# Dashcam_HAT.net
KiCad netlist of a schematic drawn in EAGLE
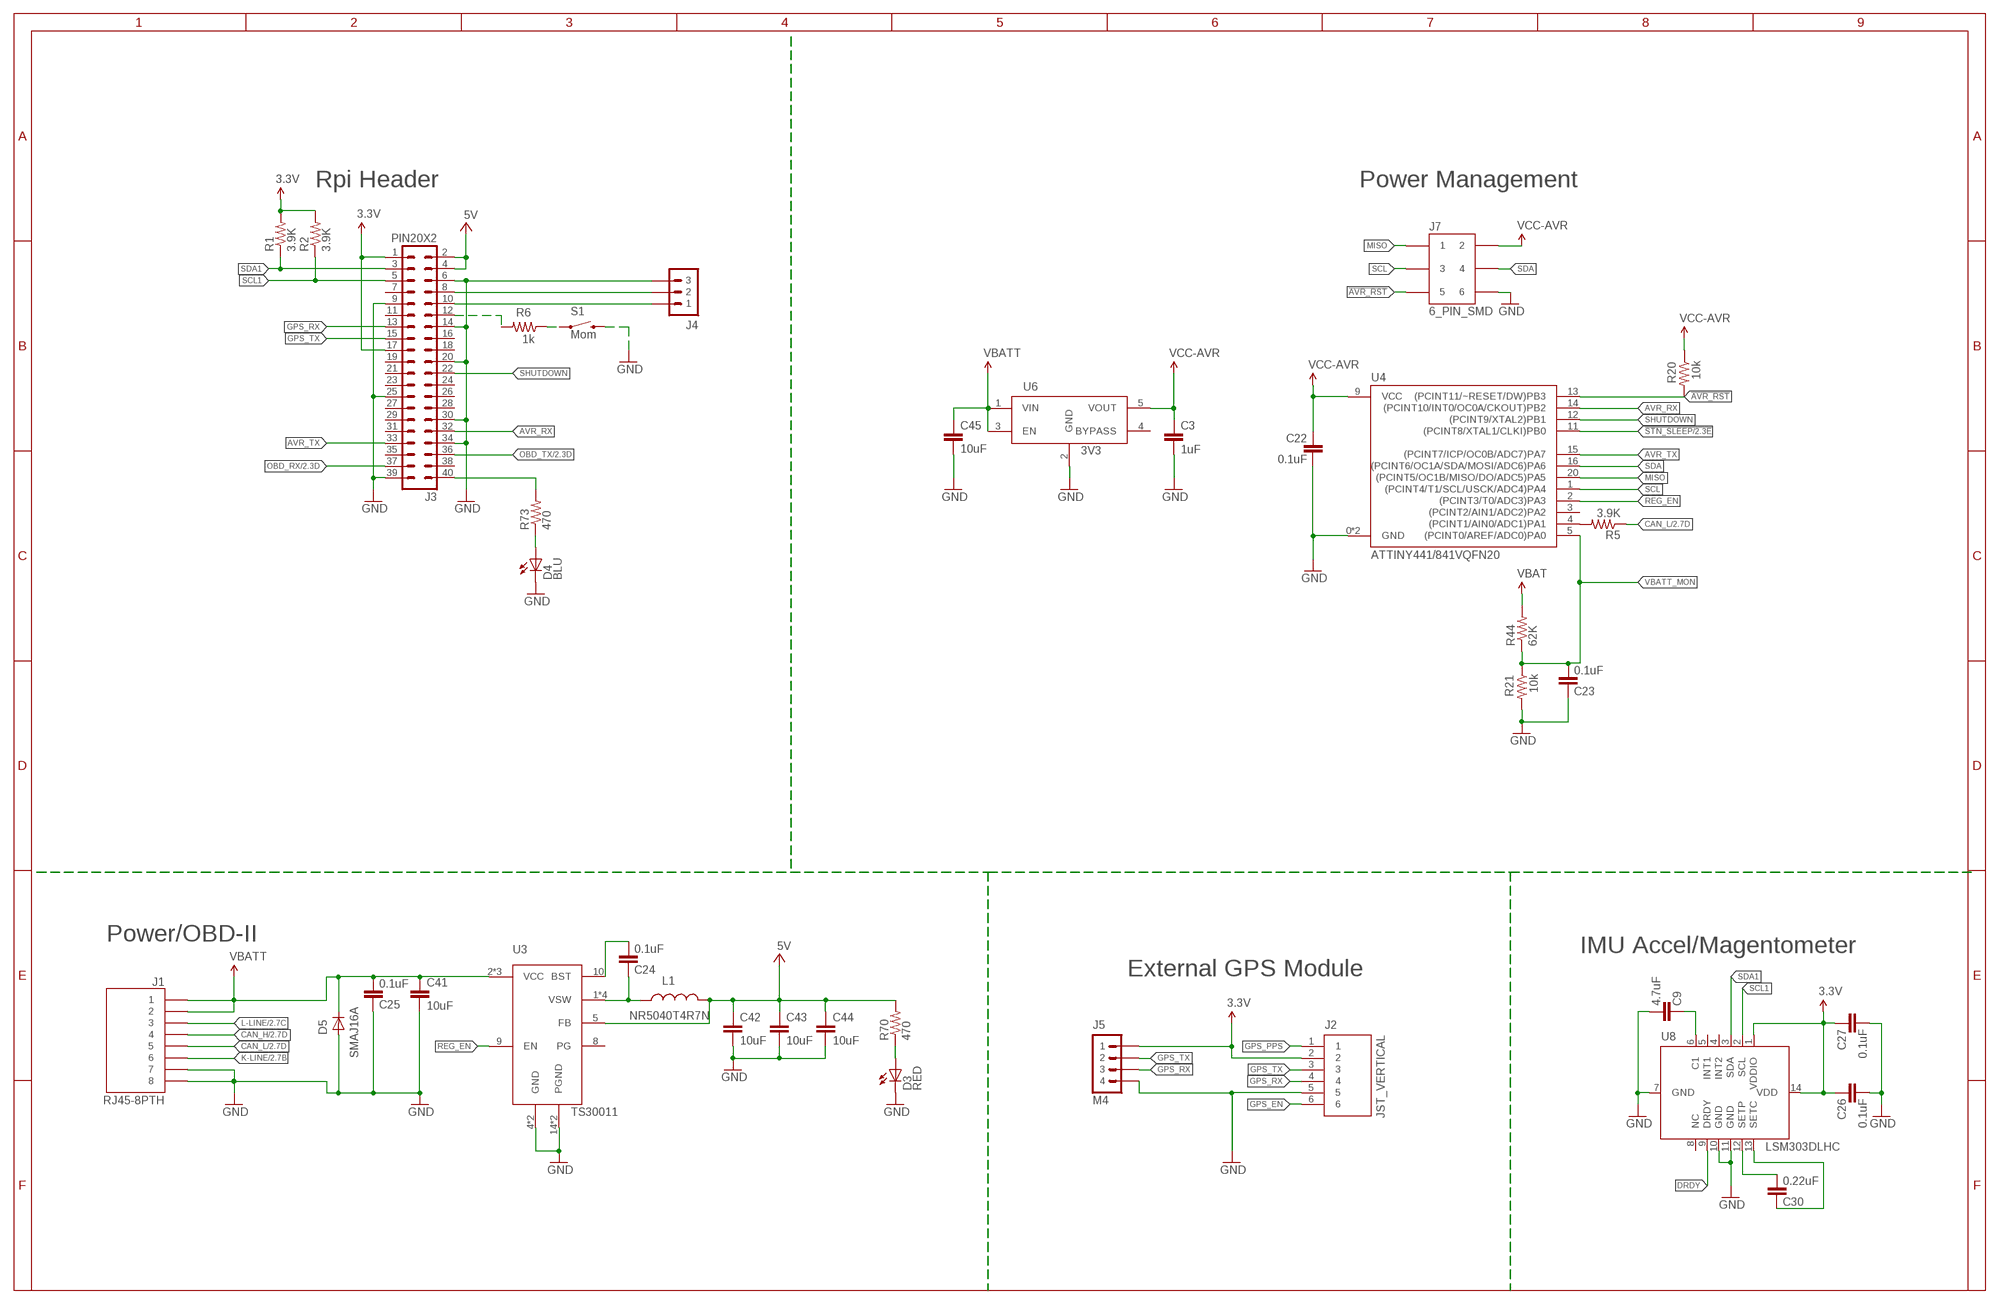
[diagram p0: schematic, sheet 1]
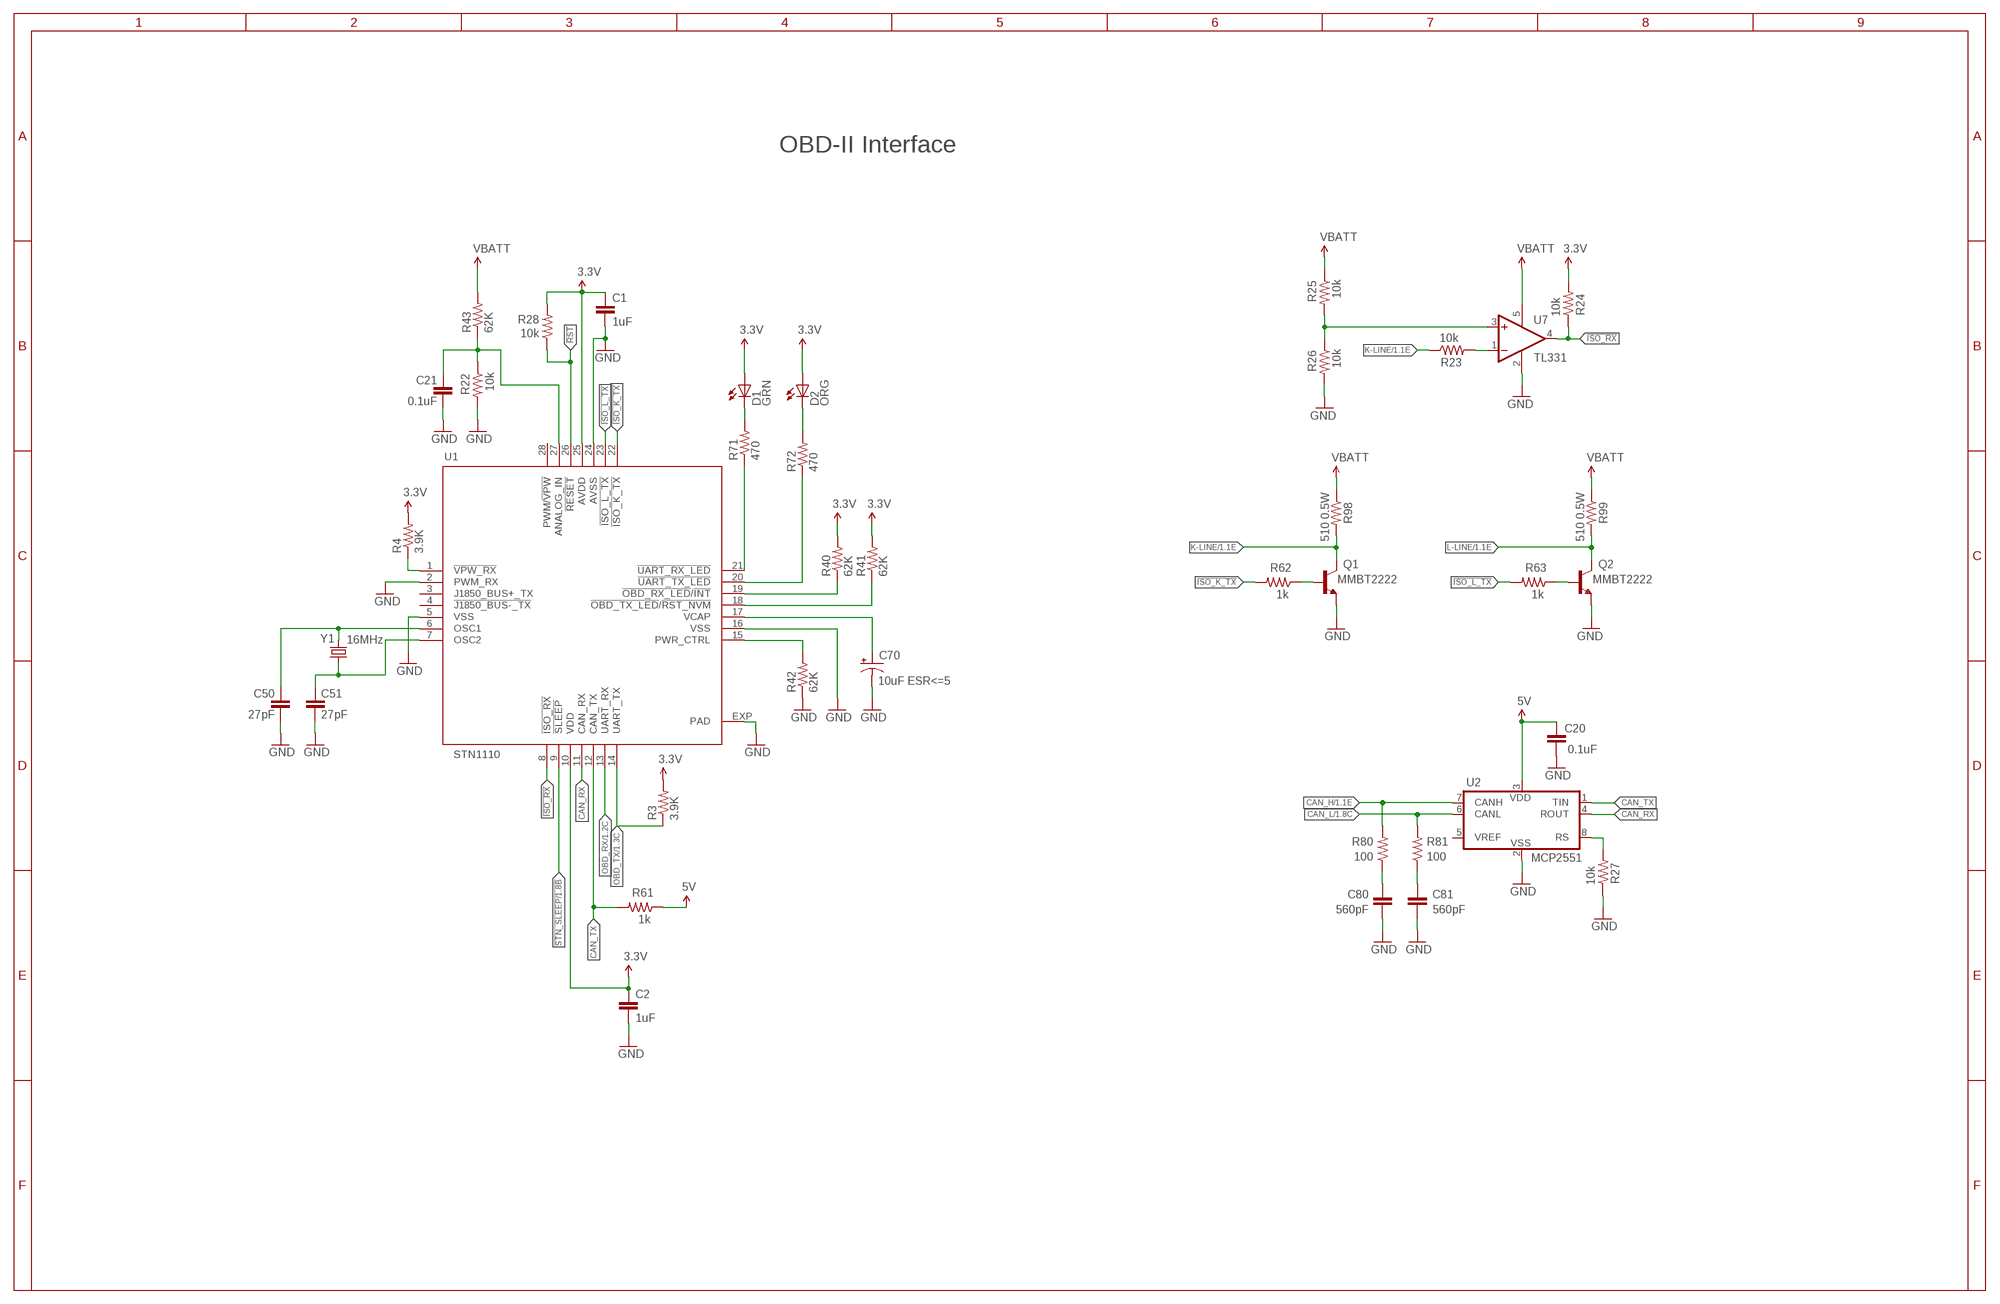
[diagram p1: schematic, sheet 2]

(export (version "E")
  (design (tool "Eeschema 10.0.6"))
  (components
    (comp (ref "C3")
      (value "1uF")
      (footprint "eagle-import:0402-CAP")
      (fields (field (name "MANUFACTURER") "Murata"))
      (libsource (lib "eagle-import") (part "CAP0402-CAP"))
    )
    (comp (ref "C9")
      (value "4.7uF")
      (footprint "eagle-import:0402-CAP")
      (fields (field (name "MANUFACTURER") "Murata"))
      (libsource (lib "eagle-import") (part "CAP0402-CAP"))
    )
    (comp (ref "C22")
      (value "0.1uF")
      (footprint "eagle-import:0402-CAP")
      (fields (field (name "MANUFACTURER") "Samsung"))
      (libsource (lib "eagle-import") (part "CAP0402-CAP"))
    )
    (comp (ref "C23")
      (value "0.1uF")
      (footprint "eagle-import:0402-CAP")
      (fields (field (name "MANUFACTURER") "Samsung"))
      (libsource (lib "eagle-import") (part "CAP0402-CAP"))
    )
    (comp (ref "C24")
      (value "0.1uF")
      (footprint "eagle-import:0402-CAP")
      (fields (field (name "MANUFACTURER") "Samsung"))
      (libsource (lib "eagle-import") (part "CAP0402-CAP"))
    )
    (comp (ref "C25")
      (value "0.1uF")
      (footprint "eagle-import:0402-CAP")
      (fields (field (name "MANUFACTURER") "Samsung"))
      (libsource (lib "eagle-import") (part "CAP0402-CAP"))
    )
    (comp (ref "C26")
      (value "0.1uF")
      (footprint "eagle-import:0402-CAP")
      (fields (field (name "MANUFACTURER") "Samsung"))
      (libsource (lib "eagle-import") (part "CAP0402-CAP"))
    )
    (comp (ref "C27")
      (value "0.1uF")
      (footprint "eagle-import:0402-CAP")
      (fields (field (name "MANUFACTURER") "Samsung"))
      (libsource (lib "eagle-import") (part "CAP0402-CAP"))
    )
    (comp (ref "C30")
      (value "0.22uF")
      (footprint "eagle-import:0402-CAP")
      (fields (field (name "MANUFACTURER") "Murata"))
      (libsource (lib "eagle-import") (part "CAP0402-CAP"))
    )
    (comp (ref "C41")
      (value "10uF")
      (footprint "eagle-import:1206")
      (fields (field (name "MANUFACTURER") "Samsung"))
      (libsource (lib "eagle-import") (part "SparkFun-Capacitors_CAP1206"))
    )
    (comp (ref "C42")
      (value "10uF")
      (footprint "eagle-import:1206")
      (fields (field (name "MANUFACTURER") "Samsung"))
      (libsource (lib "eagle-import") (part "SparkFun-Capacitors_CAP1206"))
    )
    (comp (ref "C43")
      (value "10uF")
      (footprint "eagle-import:1206")
      (fields (field (name "MANUFACTURER") "Samsung"))
      (libsource (lib "eagle-import") (part "SparkFun-Capacitors_CAP1206"))
    )
    (comp (ref "C44")
      (value "10uF")
      (footprint "eagle-import:1206")
      (fields (field (name "MANUFACTURER") "Samsung"))
      (libsource (lib "eagle-import") (part "SparkFun-Capacitors_CAP1206"))
    )
    (comp (ref "C45")
      (value "10uF")
      (footprint "eagle-import:1206")
      (fields (field (name "MANUFACTURER") "Samsung"))
      (libsource (lib "eagle-import") (part "SparkFun-Capacitors_CAP1206"))
    )
    (comp (ref "D3")
      (value "RED")
      (footprint "eagle-import:LED_0603")
      (fields (field (name "MANUFACTURER") "Lite-On Inc"))
      (libsource (lib "eagle-import") (part "LED0603"))
    )
    (comp (ref "D4")
      (value "BLU")
      (footprint "eagle-import:LED_0603")
      (fields (field (name "MANUFACTURER") "Lite-On Inc"))
      (libsource (lib "eagle-import") (part "LED0603"))
    )
    (comp (ref "D5")
      (value "SMAJ16A")
      (footprint "eagle-import:SMA")
      (fields (field (name "MANUFACTURER") "Littlefuse"))
      (libsource (lib "eagle-import") (part "DIODESMA"))
    )
    (comp (ref "J1")
      (value "RJ45-8PTH")
      (footprint "eagle-import:RJ45-8")
      (fields (field (name "MANUFACTURER") "Amphenol FCI"))
      (libsource (lib "eagle-import") (part "RJ45-8PTH"))
    )
    (comp (ref "J2")
      (value "JST_VERTICAL")
      (footprint "eagle-import:JST-6-SMD-VERT-1.0MM")
      (fields (field (name "MANUFACTURER") "JST"))
      (libsource (lib "eagle-import") (part "JST_VERTICAL"))
    )
    (comp (ref "J3")
      (value "PIN20X2")
      (footprint "eagle-import:PIN_20X2")
      (fields (field (name "MANUFACTURER") "Samtec Inc"))
      (libsource (lib "eagle-import") (part "PIN20X2"))
    )
    (comp (ref "J4")
      (value "M30.1\"_LOCK")
      (footprint "eagle-import:M3X1_LOCK")
      (libsource (lib "eagle-import") (part "M30.1{dblquote}_LOCK"))
    )
    (comp (ref "J5")
      (value "M4")
      (footprint "eagle-import:M4X1_LOCK")
      (libsource (lib "eagle-import") (part "M4"))
    )
    (comp (ref "J7")
      (value "6_PIN_SMD")
      (footprint "eagle-import:M3X2_SMD")
      (fields (field (name "MANUFACTURER") "Amphenol FCI"))
      (libsource (lib "eagle-import") (part "6_PIN_PDISMD"))
    )
    (comp (ref "L1")
      (value "NR5040T4R7N")
      (footprint "eagle-import:NR5040")
      (fields (field (name "MANUFACTURER") "Taiyo Yuden"))
      (libsource (lib "eagle-import") (part "NR5040T4R7N"))
    )
    (comp (ref "R1")
      (value "3.9K")
      (footprint "eagle-import:0402-RES")
      (fields (field (name "MANUFACTURER") "Yageo"))
      (libsource (lib "eagle-import") (part "SparkFun-Passives_RESISTOR0402-RES"))
    )
    (comp (ref "R2")
      (value "3.9K")
      (footprint "eagle-import:0402-RES")
      (fields (field (name "MANUFACTURER") "Yageo"))
      (libsource (lib "eagle-import") (part "SparkFun-Passives_RESISTOR0402-RES"))
    )
    (comp (ref "R5")
      (value "3.9K")
      (footprint "eagle-import:0402-RES")
      (fields (field (name "MANUFACTURER") "Yageo"))
      (libsource (lib "eagle-import") (part "SparkFun-Passives_RESISTOR0402-RES"))
    )
    (comp (ref "R6")
      (value "1k")
      (footprint "eagle-import:0402-RES")
      (fields (field (name "MANUFACTURER") "Yageo"))
      (libsource (lib "eagle-import") (part "RESISTOR0402-RES"))
    )
    (comp (ref "R20")
      (value "10k")
      (footprint "eagle-import:0402-RES")
      (fields (field (name "MANUFACTURER") "Yageo"))
      (libsource (lib "eagle-import") (part "RESISTOR0402-RES"))
    )
    (comp (ref "R21")
      (value "10k")
      (footprint "eagle-import:0402-RES")
      (fields (field (name "MANUFACTURER") "Yageo"))
      (libsource (lib "eagle-import") (part "RESISTOR0402-RES"))
    )
    (comp (ref "R44")
      (value "62K")
      (footprint "eagle-import:0402-RES")
      (fields (field (name "MANUFACTURER") "Yageo"))
      (libsource (lib "eagle-import") (part "RESISTOR0402-RES"))
    )
    (comp (ref "R70")
      (value "470")
      (footprint "eagle-import:0603-RES")
      (fields (field (name "MANUFACTURER") "Yageo"))
      (libsource (lib "eagle-import") (part "SparkFun-Passives_RESISTOR0603-RES"))
    )
    (comp (ref "R73")
      (value "470")
      (footprint "eagle-import:0603-RES")
      (fields (field (name "MANUFACTURER") "Yageo"))
      (libsource (lib "eagle-import") (part "SparkFun-Passives_RESISTOR0603-RES"))
    )
    (comp (ref "S1")
      (value "Mom")
      (footprint "eagle-import:TACTILE-SWITCH-1101NE")
      (fields (field (name "MANUFACTURER") "Panasonic"))
      (libsource (lib "eagle-import") (part "SWITCH-MOMENTARY-2-SMD-1101NE"))
    )
    (comp (ref "U3")
      (value "TS30011")
      (footprint "eagle-import:QFN-16")
      (fields (field (name "MANUFACTURER") "Semtech"))
      (libsource (lib "eagle-import") (part "TS30011"))
    )
    (comp (ref "U4")
      (value "ATTINY441/841VQFN20")
      (footprint "eagle-import:QFN20_0.45MM")
      (fields (field (name "MANUFACTURER") "Atmel"))
      (libsource (lib "eagle-import") (part "ATTINY441/841VQFN20"))
    )
    (comp (ref "U6")
      (value "3V3")
      (footprint "eagle-import:SOT23-5")
      (fields (field (name "MANUFACTURER") "Diodes Inc"))
      (libsource (lib "eagle-import") (part "TC1XXXSOT23-5"))
    )
    (comp (ref "U8")
      (value "LSM303DLHC")
      (footprint "eagle-import:LGA14")
      (fields (field (name "MANUFACTURER") "STMicroelectronics"))
      (libsource (lib "eagle-import") (part "LSM303DLHC"))
    )
    (comp (ref "C1")
      (value "1uF")
      (footprint "eagle-import:0402-CAP")
      (fields (field (name "MANUFACTURER") "Murata"))
      (libsource (lib "eagle-import") (part "CAP0402-CAP"))
    )
    (comp (ref "C2")
      (value "1uF")
      (footprint "eagle-import:0402-CAP")
      (fields (field (name "MANUFACTURER") "Murata"))
      (libsource (lib "eagle-import") (part "CAP0402-CAP"))
    )
    (comp (ref "C20")
      (value "0.1uF")
      (footprint "eagle-import:0402-CAP")
      (fields (field (name "MANUFACTURER") "Samsung"))
      (libsource (lib "eagle-import") (part "CAP0402-CAP"))
    )
    (comp (ref "C21")
      (value "0.1uF")
      (footprint "eagle-import:0402-CAP")
      (fields (field (name "MANUFACTURER") "Samsung"))
      (libsource (lib "eagle-import") (part "CAP0402-CAP"))
    )
    (comp (ref "C50")
      (value "27pF")
      (footprint "eagle-import:0402-CAP")
      (fields (field (name "MANUFACTURER") "Samsung"))
      (libsource (lib "eagle-import") (part "CAP0402-CAP"))
    )
    (comp (ref "C51")
      (value "27pF")
      (footprint "eagle-import:0402-CAP")
      (libsource (lib "eagle-import") (part "CAP0402-CAP"))
    )
    (comp (ref "C70")
      (value "10uF ESR<=5")
      (footprint "eagle-import:EIA3216")
      (fields (field (name "MANUFACTURER") "AVX Corporation"))
      (libsource (lib "eagle-import") (part "CAP_POL1206"))
    )
    (comp (ref "C80")
      (value "560pF")
      (footprint "eagle-import:0402-CAP")
      (fields (field (name "MANUFACTURER") "Samsung"))
      (libsource (lib "eagle-import") (part "CAP0402-CAP"))
    )
    (comp (ref "C81")
      (value "560pF")
      (footprint "eagle-import:0402-CAP")
      (fields (field (name "MANUFACTURER") "Samsung"))
      (libsource (lib "eagle-import") (part "CAP0402-CAP"))
    )
    (comp (ref "D1")
      (value "GRN")
      (footprint "eagle-import:LED_0603")
      (fields (field (name "MANUFACTURER") "Lite-On Inc"))
      (libsource (lib "eagle-import") (part "LED0603"))
    )
    (comp (ref "D2")
      (value "ORG")
      (footprint "eagle-import:LED_0603")
      (fields (field (name "MANUFACTURER") "Lite-On Inc"))
      (libsource (lib "eagle-import") (part "LED0603"))
    )
    (comp (ref "Q1")
      (value "MMBT2222")
      (footprint "eagle-import:SOT23-3")
      (fields (field (name "MANUFACTURER") "ON Semiconductor"))
      (libsource (lib "eagle-import") (part "TRANSISTOR_NPNSOT23-3"))
    )
    (comp (ref "Q2")
      (value "MMBT2222")
      (footprint "eagle-import:SOT23-3")
      (fields (field (name "MANUFACTURER") "ON Semiconductor"))
      (libsource (lib "eagle-import") (part "TRANSISTOR_NPNSOT23-3"))
    )
    (comp (ref "R3")
      (value "3.9K")
      (footprint "eagle-import:0402-RES")
      (fields (field (name "MANUFACTURER") "Yageo"))
      (libsource (lib "eagle-import") (part "SparkFun-Passives_RESISTOR0402-RES"))
    )
    (comp (ref "R4")
      (value "3.9K")
      (footprint "eagle-import:0402-RES")
      (fields (field (name "MANUFACTURER") "Yageo"))
      (libsource (lib "eagle-import") (part "SparkFun-Passives_RESISTOR0402-RES"))
    )
    (comp (ref "R22")
      (value "10k")
      (footprint "eagle-import:0402-RES")
      (fields (field (name "MANUFACTURER") "Yageo"))
      (libsource (lib "eagle-import") (part "RESISTOR0402-RES"))
    )
    (comp (ref "R23")
      (value "10k")
      (footprint "eagle-import:0402-RES")
      (fields (field (name "MANUFACTURER") "Yageo"))
      (libsource (lib "eagle-import") (part "RESISTOR0402-RES"))
    )
    (comp (ref "R24")
      (value "10k")
      (footprint "eagle-import:0402-RES")
      (fields (field (name "MANUFACTURER") "Yageo"))
      (libsource (lib "eagle-import") (part "RESISTOR0402-RES"))
    )
    (comp (ref "R25")
      (value "10k")
      (footprint "eagle-import:0402-RES")
      (fields (field (name "MANUFACTURER") "Yageo"))
      (libsource (lib "eagle-import") (part "RESISTOR0402-RES"))
    )
    (comp (ref "R26")
      (value "10k")
      (footprint "eagle-import:0402-RES")
      (fields (field (name "MANUFACTURER") "Yageo"))
      (libsource (lib "eagle-import") (part "RESISTOR0402-RES"))
    )
    (comp (ref "R27")
      (value "10k")
      (footprint "eagle-import:0402-RES")
      (fields (field (name "MANUFACTURER") "Yageo"))
      (libsource (lib "eagle-import") (part "RESISTOR0402-RES"))
    )
    (comp (ref "R28")
      (value "10k")
      (footprint "eagle-import:0402-RES")
      (libsource (lib "eagle-import") (part "RESISTOR0402-RES"))
    )
    (comp (ref "R40")
      (value "62K")
      (footprint "eagle-import:0402-RES")
      (fields (field (name "MANUFACTURER") "Yageo"))
      (libsource (lib "eagle-import") (part "RESISTOR0402-RES"))
    )
    (comp (ref "R41")
      (value "62K")
      (footprint "eagle-import:0402-RES")
      (fields (field (name "MANUFACTURER") "Yageo"))
      (libsource (lib "eagle-import") (part "RESISTOR0402-RES"))
    )
    (comp (ref "R42")
      (value "62K")
      (footprint "eagle-import:0402-RES")
      (fields (field (name "MANUFACTURER") "Yageo"))
      (libsource (lib "eagle-import") (part "RESISTOR0402-RES"))
    )
    (comp (ref "R43")
      (value "62K")
      (footprint "eagle-import:0402-RES")
      (fields (field (name "MANUFACTURER") "Yageo"))
      (libsource (lib "eagle-import") (part "RESISTOR0402-RES"))
    )
    (comp (ref "R61")
      (value "1k")
      (footprint "eagle-import:0402-RES")
      (fields (field (name "MANUFACTURER") "Yageo"))
      (libsource (lib "eagle-import") (part "RESISTOR0402-RES"))
    )
    (comp (ref "R62")
      (value "1k")
      (footprint "eagle-import:0402-RES")
      (fields (field (name "MANUFACTURER") "Yageo"))
      (libsource (lib "eagle-import") (part "RESISTOR0402-RES"))
    )
    (comp (ref "R63")
      (value "1k")
      (footprint "eagle-import:0402-RES")
      (fields (field (name "MANUFACTURER") "Yageo"))
      (libsource (lib "eagle-import") (part "RESISTOR0402-RES"))
    )
    (comp (ref "R71")
      (value "470")
      (footprint "eagle-import:0603-RES")
      (fields (field (name "MANUFACTURER") "Yageo"))
      (libsource (lib "eagle-import") (part "SparkFun-Passives_RESISTOR0603-RES"))
    )
    (comp (ref "R72")
      (value "470")
      (footprint "eagle-import:0603-RES")
      (fields (field (name "MANUFACTURER") "Yageo"))
      (libsource (lib "eagle-import") (part "SparkFun-Passives_RESISTOR0603-RES"))
    )
    (comp (ref "R80")
      (value "100")
      (footprint "eagle-import:0402-RES")
      (fields (field (name "MANUFACTURER") "Yageo"))
      (libsource (lib "eagle-import") (part "RESISTOR0402-RES"))
    )
    (comp (ref "R81")
      (value "100")
      (footprint "eagle-import:0402-RES")
      (fields (field (name "MANUFACTURER") "Yageo"))
      (libsource (lib "eagle-import") (part "RESISTOR0402-RES"))
    )
    (comp (ref "R98")
      (value "510 0.5W")
      (footprint "eagle-import:2010")
      (fields (field (name "MANUFACTURER") "Rohm Semiconductor"))
      (libsource (lib "eagle-import") (part "R-US_2010"))
    )
    (comp (ref "R99")
      (value "510 0.5W")
      (footprint "eagle-import:2010")
      (fields (field (name "MANUFACTURER") "Rohm Semiconductor"))
      (libsource (lib "eagle-import") (part "R-US_2010"))
    )
    (comp (ref "U1")
      (value "STN1110")
      (footprint "eagle-import:_STN_SCANTOOL_QFN-28-S")
      (libsource (lib "eagle-import") (part "SCANTOOL"))
    )
    (comp (ref "U2")
      (value "MCP2551")
      (footprint "eagle-import:SO-8")
      (fields (field (name "PARTNUM") "MCP2551-I/SN") (field (name "MANUFACTURER") "Microchip Technology"))
      (libsource (lib "eagle-import") (part "MCP2551-I/SN"))
    )
    (comp (ref "U7")
      (value "TL331")
      (footprint "eagle-import:DBV-R-PDSO-G5")
      (fields (field (name "MANUFACTURER") "Texas Instruments"))
      (libsource (lib "eagle-import") (part "TL331"))
    )
    (comp (ref "Y1")
      (value "16MHz")
      (footprint "eagle-import:CRYSTAL-SMD-5X3")
      (fields (field (name "MANUFACTURER") "Abracon LLC"))
      (libsource (lib "eagle-import") (part "CRYSTAL5X3"))
    )
  )
  (nets
    (net (code "1") (name "3.3V") (class "Default")
      (node (ref "C1") (pin "1") (pinfunction "1_1") (pintype "passive"))
      (node (ref "C2") (pin "1") (pinfunction "1_1") (pintype "passive"))
      (node (ref "C26") (pin "1") (pinfunction "1_1") (pintype "passive"))
      (node (ref "C27") (pin "1") (pinfunction "1_1") (pintype "passive"))
      (node (ref "D1") (pin "A") (pinfunction "A_A") (pintype "passive"))
      (node (ref "D2") (pin "A") (pinfunction "A_A") (pintype "passive"))
      (node (ref "J2") (pin "2") (pinfunction "2_2") (pintype "bidirectional"))
      (node (ref "J3") (pin "1") (pinfunction "1_1") (pintype "passive"))
      (node (ref "J3") (pin "17") (pinfunction "17_17") (pintype "passive"))
      (node (ref "J5") (pin "1") (pinfunction "1_1") (pintype "passive"))
      (node (ref "R1") (pin "2") (pinfunction "2_2") (pintype "passive"))
      (node (ref "R2") (pin "2") (pinfunction "2_2") (pintype "passive"))
      (node (ref "R24") (pin "2") (pinfunction "2_2") (pintype "passive"))
      (node (ref "R28") (pin "2") (pinfunction "2_2") (pintype "passive"))
      (node (ref "R3") (pin "2") (pinfunction "2_2") (pintype "passive"))
      (node (ref "R4") (pin "2") (pinfunction "2_2") (pintype "passive"))
      (node (ref "R40") (pin "2") (pinfunction "2_2") (pintype "passive"))
      (node (ref "R41") (pin "2") (pinfunction "2_2") (pintype "passive"))
      (node (ref "U1") (pin "10") (pinfunction "VDD_10") (pintype "power_in"))
      (node (ref "U1") (pin "25") (pinfunction "AVDD_25") (pintype "power_in"))
      (node (ref "U8") (pin "1") (pinfunction "VDDIO_1") (pintype "power_in"))
      (node (ref "U8") (pin "14") (pinfunction "VDD_14") (pintype "power_in"))
    )
    (net (code "2") (name "5V") (class "Default")
      (node (ref "C20") (pin "1") (pinfunction "1_1") (pintype "passive"))
      (node (ref "C42") (pin "1") (pinfunction "1_1") (pintype "passive"))
      (node (ref "C43") (pin "1") (pinfunction "1_1") (pintype "passive"))
      (node (ref "C44") (pin "1") (pinfunction "1_1") (pintype "passive"))
      (node (ref "J3") (pin "2") (pinfunction "2_2") (pintype "passive"))
      (node (ref "J3") (pin "4") (pinfunction "4_4") (pintype "passive"))
      (node (ref "L1") (pin "P$2") (pinfunction "2_P$2") (pintype "passive"))
      (node (ref "R61") (pin "1") (pinfunction "1_1") (pintype "passive"))
      (node (ref "R70") (pin "2") (pinfunction "2_2") (pintype "passive"))
      (node (ref "U2") (pin "3") (pinfunction "VDD_3") (pintype "power_in"))
      (node (ref "U3") (pin "5") (pinfunction "FB_5") (pintype "bidirectional"))
    )
    (net (code "3") (name "AVR_RX") (class "Default")
      (node (ref "J3") (pin "32") (pinfunction "32_32") (pintype "passive"))
      (node (ref "U4") (pin "14") (pinfunction "(PCINT10/INT0/OC0A/CKOUT)PB2_14") (pintype "bidirectional"))
    )
    (net (code "4") (name "AVR_TX") (class "Default")
      (node (ref "J3") (pin "33") (pinfunction "33_33") (pintype "passive"))
      (node (ref "U4") (pin "15") (pinfunction "(PCINT7/ICP/OC0B/ADC7)PA7_15") (pintype "bidirectional"))
    )
    (net (code "5") (name "CAN_H") (class "Default")
      (node (ref "J1") (pin "4") (pinfunction "4_4") (pintype "bidirectional"))
      (node (ref "R80") (pin "2") (pinfunction "2_2") (pintype "passive"))
      (node (ref "U2") (pin "7") (pinfunction "CANH_7") (pintype "bidirectional"))
    )
    (net (code "6") (name "CAN_L") (class "Default")
      (node (ref "J1") (pin "5") (pinfunction "5_5") (pintype "bidirectional"))
      (node (ref "R5") (pin "1") (pinfunction "1_1") (pintype "passive"))
      (node (ref "R81") (pin "2") (pinfunction "2_2") (pintype "passive"))
      (node (ref "U2") (pin "6") (pinfunction "CANL_6") (pintype "bidirectional"))
    )
    (net (code "7") (name "CAN_RX") (class "Default")
      (node (ref "U1") (pin "11") (pinfunction "CAN_RX_11") (pintype "input"))
      (node (ref "U2") (pin "4") (pinfunction "ROUT_4") (pintype "output"))
    )
    (net (code "8") (name "CAN_TX") (class "Default")
      (node (ref "R61") (pin "2") (pinfunction "2_2") (pintype "passive"))
      (node (ref "U1") (pin "12") (pinfunction "CAN_TX_12") (pintype "output"))
      (node (ref "U2") (pin "1") (pinfunction "TIN_1") (pintype "input"))
    )
    (net (code "9") (name "DRDY") (class "Default")
      (node (ref "U8") (pin "9") (pinfunction "DRDY_9") (pintype "output"))
    )
    (net (code "10") (name "GND") (class "Default")
      (node (ref "C1") (pin "2") (pinfunction "2_2") (pintype "passive"))
      (node (ref "C2") (pin "2") (pinfunction "2_2") (pintype "passive"))
      (node (ref "C20") (pin "2") (pinfunction "2_2") (pintype "passive"))
      (node (ref "C21") (pin "2") (pinfunction "2_2") (pintype "passive"))
      (node (ref "C22") (pin "2") (pinfunction "2_2") (pintype "passive"))
      (node (ref "C23") (pin "1") (pinfunction "1_1") (pintype "passive"))
      (node (ref "C25") (pin "1") (pinfunction "1_1") (pintype "passive"))
      (node (ref "C26") (pin "2") (pinfunction "2_2") (pintype "passive"))
      (node (ref "C27") (pin "2") (pinfunction "2_2") (pintype "passive"))
      (node (ref "C3") (pin "2") (pinfunction "2_2") (pintype "passive"))
      (node (ref "C41") (pin "2") (pinfunction "2_2") (pintype "passive"))
      (node (ref "C42") (pin "2") (pinfunction "2_2") (pintype "passive"))
      (node (ref "C43") (pin "2") (pinfunction "2_2") (pintype "passive"))
      (node (ref "C44") (pin "2") (pinfunction "2_2") (pintype "passive"))
      (node (ref "C45") (pin "2") (pinfunction "2_2") (pintype "passive"))
      (node (ref "C50") (pin "2") (pinfunction "2_2") (pintype "passive"))
      (node (ref "C51") (pin "2") (pinfunction "2_2") (pintype "passive"))
      (node (ref "C70") (pin "C") (pinfunction "-_C") (pintype "passive"))
      (node (ref "C80") (pin "2") (pinfunction "2_2") (pintype "passive"))
      (node (ref "C81") (pin "2") (pinfunction "2_2") (pintype "passive"))
      (node (ref "C9") (pin "2") (pinfunction "2_2") (pintype "passive"))
      (node (ref "D3") (pin "C") (pinfunction "C_C") (pintype "passive"))
      (node (ref "D4") (pin "C") (pinfunction "C_C") (pintype "passive"))
      (node (ref "D5") (pin "A") (pinfunction "A_A") (pintype "passive"))
      (node (ref "J1") (pin "7") (pinfunction "7_7") (pintype "bidirectional"))
      (node (ref "J1") (pin "8") (pinfunction "8_8") (pintype "bidirectional"))
      (node (ref "J2") (pin "5") (pinfunction "5_5") (pintype "bidirectional"))
      (node (ref "J3") (pin "14") (pinfunction "14_14") (pintype "passive"))
      (node (ref "J3") (pin "20") (pinfunction "20_20") (pintype "passive"))
      (node (ref "J3") (pin "25") (pinfunction "25_25") (pintype "passive"))
      (node (ref "J3") (pin "30") (pinfunction "30_30") (pintype "passive"))
      (node (ref "J3") (pin "34") (pinfunction "34_34") (pintype "passive"))
      (node (ref "J3") (pin "39") (pinfunction "39_39") (pintype "passive"))
      (node (ref "J3") (pin "6") (pinfunction "6_6") (pintype "passive"))
      (node (ref "J3") (pin "9") (pinfunction "9_9") (pintype "passive"))
      (node (ref "J4") (pin "3") (pinfunction "3_3") (pintype "passive"))
      (node (ref "J5") (pin "4") (pinfunction "4_4") (pintype "passive"))
      (node (ref "J7") (pin "P$6") (pinfunction "6_P$6") (pintype "bidirectional"))
      (node (ref "Q1") (pin "2") (pinfunction "E_2") (pintype "passive"))
      (node (ref "Q2") (pin "2") (pinfunction "E_2") (pintype "passive"))
      (node (ref "R21") (pin "2") (pinfunction "2_2") (pintype "passive"))
      (node (ref "R22") (pin "2") (pinfunction "2_2") (pintype "passive"))
      (node (ref "R26") (pin "2") (pinfunction "2_2") (pintype "passive"))
      (node (ref "R27") (pin "1") (pinfunction "1_1") (pintype "passive"))
      (node (ref "R42") (pin "1") (pinfunction "1_1") (pintype "passive"))
      (node (ref "S1") (pin "P$2") (pinfunction "2_P$2") (pintype "passive"))
      (node (ref "U1") (pin "16") (pinfunction "VSS_16") (pintype "power_in"))
      (node (ref "U1") (pin "2") (pinfunction "PWM_RX_2") (pintype "input"))
      (node (ref "U1") (pin "24") (pinfunction "AVSS_24") (pintype "power_in"))
      (node (ref "U1") (pin "5") (pinfunction "VSS_5") (pintype "power_in"))
      (node (ref "U1") (pin "EXP") (pinfunction "PAD_EXP") (pintype "passive"))
      (node (ref "U2") (pin "2") (pinfunction "VSS_2") (pintype "power_in"))
      (node (ref "U3") (pin "14") (pinfunction "PGND_14") (pintype "bidirectional"))
      (node (ref "U3") (pin "15") (pinfunction "PGND_15") (pintype "bidirectional"))
      (node (ref "U3") (pin "4") (pinfunction "GND_4") (pintype "bidirectional"))
      (node (ref "U3") (pin "EXP") (pinfunction "GND_EXP") (pintype "bidirectional"))
      (node (ref "U4") (pin "0") (pinfunction "GND_0") (pintype "bidirectional"))
      (node (ref "U4") (pin "8") (pinfunction "GND_8") (pintype "bidirectional"))
      (node (ref "U6") (pin "2") (pinfunction "GND_2") (pintype "bidirectional"))
      (node (ref "U7") (pin "2") (pinfunction "GND_2") (pintype "power_in"))
      (node (ref "U8") (pin "10") (pinfunction "GND_10") (pintype "power_in"))
      (node (ref "U8") (pin "11") (pinfunction "GND_11") (pintype "power_in"))
      (node (ref "U8") (pin "7") (pinfunction "GND_7") (pintype "power_in"))
    )
    (net (code "11") (name "GPS_EN") (class "Default")
      (node (ref "J2") (pin "6") (pinfunction "6_6") (pintype "bidirectional"))
    )
    (net (code "12") (name "GPS_PPS") (class "Default")
      (node (ref "J2") (pin "1") (pinfunction "1_1") (pintype "bidirectional"))
    )
    (net (code "13") (name "GPS_RX") (class "Default")
      (node (ref "J2") (pin "4") (pinfunction "4_4") (pintype "bidirectional"))
      (node (ref "J3") (pin "13") (pinfunction "13_13") (pintype "passive"))
      (node (ref "J5") (pin "3") (pinfunction "3_3") (pintype "passive"))
    )
    (net (code "14") (name "GPS_TX") (class "Default")
      (node (ref "J2") (pin "3") (pinfunction "3_3") (pintype "bidirectional"))
      (node (ref "J3") (pin "15") (pinfunction "15_15") (pintype "passive"))
      (node (ref "J5") (pin "2") (pinfunction "2_2") (pintype "passive"))
    )
    (net (code "15") (name "K-LINE") (class "Default")
      (node (ref "J1") (pin "6") (pinfunction "6_6") (pintype "bidirectional"))
      (node (ref "Q1") (pin "3") (pinfunction "C_3") (pintype "passive"))
      (node (ref "R23") (pin "1") (pinfunction "1_1") (pintype "passive"))
      (node (ref "R98") (pin "2") (pinfunction "2_2") (pintype "passive"))
    )
    (net (code "16") (name "L-LINE") (class "Default")
      (node (ref "J1") (pin "3") (pinfunction "3_3") (pintype "bidirectional"))
      (node (ref "Q2") (pin "3") (pinfunction "C_3") (pintype "passive"))
      (node (ref "R99") (pin "2") (pinfunction "2_2") (pintype "passive"))
    )
    (net (code "17") (name "MISO") (class "Default")
      (node (ref "J7") (pin "P$1") (pinfunction "1_P$1") (pintype "bidirectional"))
      (node (ref "U4") (pin "20") (pinfunction "(PCINT5/OC1B/MISO/DO/ADC5)PA5_20") (pintype "bidirectional"))
    )
    (net (code "18") (name "Net-(C70-+)") (class "Default")
      (node (ref "C70") (pin "A") (pinfunction "+_A") (pintype "passive"))
      (node (ref "U1") (pin "17") (pinfunction "VCAP_17") (pintype "power_in"))
    )
    (net (code "19") (name "Net-(C80-Pad1)") (class "Default")
      (node (ref "C80") (pin "1") (pinfunction "1_1") (pintype "passive"))
      (node (ref "R80") (pin "1") (pinfunction "1_1") (pintype "passive"))
    )
    (net (code "20") (name "Net-(C81-Pad1)") (class "Default")
      (node (ref "C81") (pin "1") (pinfunction "1_1") (pintype "passive"))
      (node (ref "R81") (pin "1") (pinfunction "1_1") (pintype "passive"))
    )
    (net (code "21") (name "Net-(D1-PadC)") (class "Default")
      (node (ref "D1") (pin "C") (pinfunction "C_C") (pintype "passive"))
      (node (ref "R71") (pin "2") (pinfunction "2_2") (pintype "passive"))
    )
    (net (code "22") (name "Net-(D2-PadC)") (class "Default")
      (node (ref "D2") (pin "C") (pinfunction "C_C") (pintype "passive"))
      (node (ref "R72") (pin "2") (pinfunction "2_2") (pintype "passive"))
    )
    (net (code "23") (name "Net-(D3-PadA)") (class "Default")
      (node (ref "D3") (pin "A") (pinfunction "A_A") (pintype "passive"))
      (node (ref "R70") (pin "1") (pinfunction "1_1") (pintype "passive"))
    )
    (net (code "24") (name "Net-(D4-PadA)") (class "Default")
      (node (ref "D4") (pin "A") (pinfunction "A_A") (pintype "passive"))
      (node (ref "R73") (pin "1") (pinfunction "1_1") (pintype "passive"))
    )
    (net (code "25") (name "Net-(J3-Pad8)") (class "Default")
      (node (ref "J3") (pin "8") (pinfunction "8_8") (pintype "passive"))
      (node (ref "J4") (pin "2") (pinfunction "2_2") (pintype "passive"))
    )
    (net (code "26") (name "Net-(J3-Pad10)") (class "Default")
      (node (ref "J3") (pin "10") (pinfunction "10_10") (pintype "passive"))
      (node (ref "J4") (pin "1") (pinfunction "1_1") (pintype "passive"))
    )
    (net (code "27") (name "Net-(J3-Pad12)") (class "Default")
      (node (ref "J3") (pin "12") (pinfunction "12_12") (pintype "passive"))
      (node (ref "R6") (pin "2") (pinfunction "2_2") (pintype "passive"))
    )
    (net (code "28") (name "Net-(J3-Pad40)") (class "Default")
      (node (ref "J3") (pin "40") (pinfunction "40_40") (pintype "passive"))
      (node (ref "R73") (pin "2") (pinfunction "2_2") (pintype "passive"))
    )
    (net (code "29") (name "Net-(L1-1)") (class "Default")
      (node (ref "C24") (pin "1") (pinfunction "1_1") (pintype "passive"))
      (node (ref "L1") (pin "P$1") (pinfunction "1_P$1") (pintype "passive"))
      (node (ref "U3") (pin "1") (pinfunction "VSW_1") (pintype "bidirectional"))
      (node (ref "U3") (pin "12") (pinfunction "VSW_12") (pintype "bidirectional"))
      (node (ref "U3") (pin "13") (pinfunction "VSW_13") (pintype "bidirectional"))
      (node (ref "U3") (pin "16") (pinfunction "VSW_16") (pintype "bidirectional"))
    )
    (net (code "30") (name "Net-(Q1-B)") (class "Default")
      (node (ref "Q1") (pin "1") (pinfunction "B_1") (pintype "passive"))
      (node (ref "R62") (pin "1") (pinfunction "1_1") (pintype "passive"))
    )
    (net (code "31") (name "Net-(Q2-B)") (class "Default")
      (node (ref "Q2") (pin "1") (pinfunction "B_1") (pintype "passive"))
      (node (ref "R63") (pin "1") (pinfunction "1_1") (pintype "passive"))
    )
    (net (code "32") (name "Net-(S1-1)") (class "Default")
      (node (ref "R6") (pin "1") (pinfunction "1_1") (pintype "passive"))
      (node (ref "S1") (pin "P$1") (pinfunction "1_P$1") (pintype "passive"))
    )
    (net (code "33") (name "Net-(U1-ANALOG_IN)") (class "Default")
      (node (ref "C21") (pin "1") (pinfunction "1_1") (pintype "passive"))
      (node (ref "R22") (pin "1") (pinfunction "1_1") (pintype "passive"))
      (node (ref "R43") (pin "1") (pinfunction "1_1") (pintype "passive"))
      (node (ref "U1") (pin "27") (pinfunction "ANALOG_IN_27") (pintype "input"))
    )
    (net (code "34") (name "Net-(U1-OSC1)") (class "Default")
      (node (ref "C50") (pin "1") (pinfunction "1_1") (pintype "passive"))
      (node (ref "U1") (pin "6") (pinfunction "OSC1_6") (pintype "input"))
      (node (ref "Y1") (pin "3") (pinfunction "2_3") (pintype "passive"))
    )
    (net (code "35") (name "Net-(U1-OSC2)") (class "Default")
      (node (ref "C51") (pin "1") (pinfunction "1_1") (pintype "passive"))
      (node (ref "U1") (pin "7") (pinfunction "OSC2_7") (pintype "output"))
      (node (ref "Y1") (pin "1") (pinfunction "1_1") (pintype "passive"))
    )
    (net (code "36") (name "Net-(U1-PWR_CTRL)") (class "Default")
      (node (ref "R42") (pin "2") (pinfunction "2_2") (pintype "passive"))
      (node (ref "U1") (pin "15") (pinfunction "PWR_CTRL_15") (pintype "output"))
    )
    (net (code "37") (name "Net-(U1-~{OBD_RX_LED}{slash}~{INT})") (class "Default")
      (node (ref "R40") (pin "1") (pinfunction "1_1") (pintype "passive"))
      (node (ref "U1") (pin "19") (pinfunction "~{OBD_RX_LED}/~{INT}_19") (pintype "output"))
    )
    (net (code "38") (name "Net-(U1-~{OBD_TX_LED}{slash}~{RST_NVM})") (class "Default")
      (node (ref "R41") (pin "1") (pinfunction "1_1") (pintype "passive"))
      (node (ref "U1") (pin "18") (pinfunction "~{OBD_TX_LED}/~{RST_NVM}_18") (pintype "bidirectional"))
    )
    (net (code "39") (name "Net-(U1-~{UART_RX_LED})") (class "Default")
      (node (ref "R71") (pin "1") (pinfunction "1_1") (pintype "passive"))
      (node (ref "U1") (pin "21") (pinfunction "~{UART_RX_LED}_21") (pintype "output"))
    )
    (net (code "40") (name "Net-(U1-~{UART_TX_LED})") (class "Default")
      (node (ref "R72") (pin "1") (pinfunction "1_1") (pintype "passive"))
      (node (ref "U1") (pin "20") (pinfunction "~{UART_TX_LED}_20") (pintype "output"))
    )
    (net (code "41") (name "Net-(U1-~{VPW_RX})") (class "Default")
      (node (ref "R4") (pin "1") (pinfunction "1_1") (pintype "passive"))
      (node (ref "U1") (pin "1") (pinfunction "~{VPW_RX}_1") (pintype "input"))
    )
    (net (code "42") (name "Net-(U2-RS)") (class "Default")
      (node (ref "R27") (pin "2") (pinfunction "2_2") (pintype "passive"))
      (node (ref "U2") (pin "8") (pinfunction "RS_8") (pintype "input"))
    )
    (net (code "43") (name "Net-(U3-BST)") (class "Default")
      (node (ref "C24") (pin "2") (pinfunction "2_2") (pintype "passive"))
      (node (ref "U3") (pin "10") (pinfunction "BST_10") (pintype "bidirectional"))
    )
    (net (code "44") (name "Net-(U4-(PCINT1{slash}AIN0{slash}ADC1)PA1)") (class "Default")
      (node (ref "R5") (pin "2") (pinfunction "2_2") (pintype "passive"))
      (node (ref "U4") (pin "4") (pinfunction "(PCINT1/AIN0/ADC1)PA1_4") (pintype "bidirectional"))
    )
    (net (code "45") (name "Net-(U7-+IN)") (class "Default")
      (node (ref "R25") (pin "2") (pinfunction "2_2") (pintype "passive"))
      (node (ref "R26") (pin "1") (pinfunction "1_1") (pintype "passive"))
      (node (ref "U7") (pin "3") (pinfunction "+IN_3") (pintype "input"))
    )
    (net (code "46") (name "Net-(U7--IN)") (class "Default")
      (node (ref "R23") (pin "2") (pinfunction "2_2") (pintype "passive"))
      (node (ref "U7") (pin "1") (pinfunction "-IN_1") (pintype "input"))
    )
    (net (code "47") (name "Net-(U8-C1)") (class "Default")
      (node (ref "C9") (pin "1") (pinfunction "1_1") (pintype "passive"))
      (node (ref "U8") (pin "6") (pinfunction "C1_6") (pintype "bidirectional"))
    )
    (net (code "48") (name "Net-(U8-SETC)") (class "Default")
      (node (ref "C30") (pin "1") (pinfunction "1_1") (pintype "passive"))
      (node (ref "U8") (pin "13") (pinfunction "SETC_13") (pintype "bidirectional"))
    )
    (net (code "49") (name "Net-(U8-SETP)") (class "Default")
      (node (ref "C30") (pin "2") (pinfunction "2_2") (pintype "passive"))
      (node (ref "U8") (pin "12") (pinfunction "SETP_12") (pintype "bidirectional"))
    )
    (net (code "50") (name "OBD_RX") (class "Default")
      (node (ref "J3") (pin "37") (pinfunction "37_37") (pintype "passive"))
      (node (ref "U1") (pin "13") (pinfunction "UART_RX_13") (pintype "input"))
    )
    (net (code "51") (name "OBD_TX") (class "Default")
      (node (ref "J3") (pin "36") (pinfunction "36_36") (pintype "passive"))
      (node (ref "R3") (pin "1") (pinfunction "1_1") (pintype "passive"))
      (node (ref "U1") (pin "14") (pinfunction "UART_TX_14") (pintype "output"))
    )
    (net (code "52") (name "REG_EN") (class "Default")
      (node (ref "U3") (pin "9") (pinfunction "EN_9") (pintype "bidirectional"))
      (node (ref "U4") (pin "2") (pinfunction "(PCINT3/T0/ADC3)PA3_2") (pintype "bidirectional"))
    )
    (net (code "53") (name "SCL") (class "Default")
      (node (ref "J7") (pin "P$3") (pinfunction "3_P$3") (pintype "bidirectional"))
      (node (ref "U4") (pin "1") (pinfunction "(PCINT4/T1/SCL/USCK/ADC4)PA4_1") (pintype "bidirectional"))
    )
    (net (code "54") (name "SCL1") (class "Default")
      (node (ref "J3") (pin "5") (pinfunction "5_5") (pintype "passive"))
      (node (ref "R2") (pin "1") (pinfunction "1_1") (pintype "passive"))
      (node (ref "U8") (pin "2") (pinfunction "SCL_2") (pintype "bidirectional"))
    )
    (net (code "55") (name "SDA") (class "Default")
      (node (ref "J7") (pin "P$4") (pinfunction "4_P$4") (pintype "bidirectional"))
      (node (ref "U4") (pin "16") (pinfunction "(PCINT6/OC1A/SDA/MOSI/ADC6)PA6_16") (pintype "bidirectional"))
    )
    (net (code "56") (name "SDA1") (class "Default")
      (node (ref "J3") (pin "3") (pinfunction "3_3") (pintype "passive"))
      (node (ref "R1") (pin "1") (pinfunction "1_1") (pintype "passive"))
      (node (ref "U8") (pin "3") (pinfunction "SDA_3") (pintype "bidirectional"))
    )
    (net (code "57") (name "SHUTDOWN") (class "Default")
      (node (ref "J3") (pin "22") (pinfunction "22_22") (pintype "passive"))
      (node (ref "U4") (pin "12") (pinfunction "(PCINT9/XTAL2)PB1_12") (pintype "bidirectional"))
    )
    (net (code "58") (name "VBATT") (class "Default")
      (node (ref "C25") (pin "2") (pinfunction "2_2") (pintype "passive"))
      (node (ref "C41") (pin "1") (pinfunction "1_1") (pintype "passive"))
      (node (ref "C45") (pin "1") (pinfunction "1_1") (pintype "passive"))
      (node (ref "D5") (pin "K") (pinfunction "C_K") (pintype "passive"))
      (node (ref "J1") (pin "1") (pinfunction "1_1") (pintype "bidirectional"))
      (node (ref "J1") (pin "2") (pinfunction "2_2") (pintype "bidirectional"))
      (node (ref "R25") (pin "1") (pinfunction "1_1") (pintype "passive"))
      (node (ref "R43") (pin "2") (pinfunction "2_2") (pintype "passive"))
      (node (ref "R44") (pin "2") (pinfunction "2_2") (pintype "passive"))
      (node (ref "R98") (pin "1") (pinfunction "1_1") (pintype "passive"))
      (node (ref "R99") (pin "1") (pinfunction "1_1") (pintype "passive"))
      (node (ref "U3") (pin "11") (pinfunction "VCC_11") (pintype "bidirectional"))
      (node (ref "U3") (pin "2") (pinfunction "VCC_2") (pintype "bidirectional"))
      (node (ref "U3") (pin "3") (pinfunction "VCC_3") (pintype "bidirectional"))
      (node (ref "U6") (pin "1") (pinfunction "VIN_1") (pintype "bidirectional"))
      (node (ref "U6") (pin "3") (pinfunction "EN_3") (pintype "bidirectional"))
      (node (ref "U7") (pin "5") (pinfunction "V+_5") (pintype "power_in"))
    )
    (net (code "59") (name "VBATT_MON") (class "Default")
      (node (ref "C23") (pin "2") (pinfunction "2_2") (pintype "passive"))
      (node (ref "R21") (pin "1") (pinfunction "1_1") (pintype "passive"))
      (node (ref "R44") (pin "1") (pinfunction "1_1") (pintype "passive"))
      (node (ref "U4") (pin "5") (pinfunction "(PCINT0/AREF/ADC0)PA0_5") (pintype "bidirectional"))
    )
    (net (code "60") (name "VCC-AVR") (class "Default")
      (node (ref "C22") (pin "1") (pinfunction "1_1") (pintype "passive"))
      (node (ref "C3") (pin "1") (pinfunction "1_1") (pintype "passive"))
      (node (ref "J7") (pin "P$2") (pinfunction "2_P$2") (pintype "bidirectional"))
      (node (ref "R20") (pin "1") (pinfunction "1_1") (pintype "passive"))
      (node (ref "U4") (pin "9") (pinfunction "VCC_9") (pintype "bidirectional"))
      (node (ref "U6") (pin "5") (pinfunction "VOUT_5") (pintype "bidirectional"))
    )
    (net (code "61") (name "unconnected-(J3-Pad7)") (class "Default")
      (node (ref "J3") (pin "7") (pinfunction "7_7") (pintype "passive"))
    )
    (net (code "62") (name "unconnected-(J3-Pad11)") (class "Default")
      (node (ref "J3") (pin "11") (pinfunction "11_11") (pintype "passive"))
    )
    (net (code "63") (name "unconnected-(J3-Pad16)") (class "Default")
      (node (ref "J3") (pin "16") (pinfunction "16_16") (pintype "passive"))
    )
    (net (code "64") (name "unconnected-(J3-Pad18)") (class "Default")
      (node (ref "J3") (pin "18") (pinfunction "18_18") (pintype "passive"))
    )
    (net (code "65") (name "unconnected-(J3-Pad19)") (class "Default")
      (node (ref "J3") (pin "19") (pinfunction "19_19") (pintype "passive"))
    )
    (net (code "66") (name "unconnected-(J3-Pad21)") (class "Default")
      (node (ref "J3") (pin "21") (pinfunction "21_21") (pintype "passive"))
    )
    (net (code "67") (name "unconnected-(J3-Pad23)") (class "Default")
      (node (ref "J3") (pin "23") (pinfunction "23_23") (pintype "passive"))
    )
    (net (code "68") (name "unconnected-(J3-Pad24)") (class "Default")
      (node (ref "J3") (pin "24") (pinfunction "24_24") (pintype "passive"))
    )
    (net (code "69") (name "unconnected-(J3-Pad26)") (class "Default")
      (node (ref "J3") (pin "26") (pinfunction "26_26") (pintype "passive"))
    )
    (net (code "70") (name "unconnected-(J3-Pad27)") (class "Default")
      (node (ref "J3") (pin "27") (pinfunction "27_27") (pintype "passive"))
    )
    (net (code "71") (name "unconnected-(J3-Pad28)") (class "Default")
      (node (ref "J3") (pin "28") (pinfunction "28_28") (pintype "passive"))
    )
    (net (code "72") (name "unconnected-(J3-Pad29)") (class "Default")
      (node (ref "J3") (pin "29") (pinfunction "29_29") (pintype "passive"))
    )
    (net (code "73") (name "unconnected-(J3-Pad31)") (class "Default")
      (node (ref "J3") (pin "31") (pinfunction "31_31") (pintype "passive"))
    )
    (net (code "74") (name "unconnected-(J3-Pad35)") (class "Default")
      (node (ref "J3") (pin "35") (pinfunction "35_35") (pintype "passive"))
    )
    (net (code "75") (name "unconnected-(J3-Pad38)") (class "Default")
      (node (ref "J3") (pin "38") (pinfunction "38_38") (pintype "passive"))
    )
    (net (code "76") (name "unconnected-(U1-J1850_BUS+_TX-Pad3)") (class "Default")
      (node (ref "U1") (pin "3") (pinfunction "J1850_BUS+_TX_3") (pintype "output"))
    )
    (net (code "77") (name "unconnected-(U1-PWM{slash}~{VPW}-Pad28)") (class "Default")
      (node (ref "U1") (pin "28") (pinfunction "PWM/~{VPW}_28") (pintype "output"))
    )
    (net (code "78") (name "unconnected-(U1-~{J1850_BUS-_TX}-Pad4)") (class "Default")
      (node (ref "U1") (pin "4") (pinfunction "~{J1850_BUS-_TX}_4") (pintype "output"))
    )
    (net (code "79") (name "unconnected-(U2-VREF-Pad5)") (class "Default")
      (node (ref "U2") (pin "5") (pinfunction "VREF_5") (pintype "output"))
    )
    (net (code "80") (name "unconnected-(U3-PG-Pad8)") (class "Default")
      (node (ref "U3") (pin "8") (pinfunction "PG_8") (pintype "bidirectional"))
    )
    (net (code "81") (name "unconnected-(U4-(PCINT2{slash}AIN1{slash}ADC2)PA2-Pad3)") (class "Default")
      (node (ref "U4") (pin "3") (pinfunction "(PCINT2/AIN1/ADC2)PA2_3") (pintype "bidirectional"))
    )
    (net (code "82") (name "unconnected-(U6-BYPASS-Pad4)") (class "Default")
      (node (ref "U6") (pin "4") (pinfunction "BYPASS_4") (pintype "bidirectional"))
    )
    (net (code "83") (name "unconnected-(U8-INT1-Pad5)") (class "Default")
      (node (ref "U8") (pin "5") (pinfunction "INT1_5") (pintype "output"))
    )
    (net (code "84") (name "unconnected-(U8-INT2-Pad4)") (class "Default")
      (node (ref "U8") (pin "4") (pinfunction "INT2_4") (pintype "output"))
    )
    (net (code "85") (name "unconnected-(U8-NC-Pad8)") (class "Default")
      (node (ref "U8") (pin "8") (pinfunction "NC_8") (pintype "bidirectional"))
    )
    (net (code "86") (name "~{AVR_RST}") (class "Default")
      (node (ref "J7") (pin "P$5") (pinfunction "5_P$5") (pintype "bidirectional"))
      (node (ref "R20") (pin "2") (pinfunction "2_2") (pintype "passive"))
      (node (ref "U4") (pin "13") (pinfunction "(PCINT11/~{RESET/DW})PB3_13") (pintype "bidirectional"))
    )
    (net (code "87") (name "~{ISO_K_TX}") (class "Default")
      (node (ref "R62") (pin "2") (pinfunction "2_2") (pintype "passive"))
      (node (ref "U1") (pin "22") (pinfunction "~{ISO_K_TX}_22") (pintype "output"))
    )
    (net (code "88") (name "~{ISO_L_TX}") (class "Default")
      (node (ref "R63") (pin "2") (pinfunction "2_2") (pintype "passive"))
      (node (ref "U1") (pin "23") (pinfunction "~{ISO_L_TX}_23") (pintype "output"))
    )
    (net (code "89") (name "~{ISO_RX}") (class "Default")
      (node (ref "R24") (pin "1") (pinfunction "1_1") (pintype "passive"))
      (node (ref "U1") (pin "8") (pinfunction "~{ISO_RX}_8") (pintype "input"))
      (node (ref "U7") (pin "4") (pinfunction "OUT_4") (pintype "output"))
    )
    (net (code "90") (name "~{RST}") (class "Default")
      (node (ref "R28") (pin "1") (pinfunction "1_1") (pintype "passive"))
      (node (ref "U1") (pin "26") (pinfunction "~{RESET}_26") (pintype "input"))
    )
    (net (code "91") (name "~{STN_SLEEP}") (class "Default")
      (node (ref "U1") (pin "9") (pinfunction "~{SLEEP}_9") (pintype "input"))
      (node (ref "U4") (pin "11") (pinfunction "(PCINT8/XTAL1/CLKI)PB0_11") (pintype "bidirectional"))
    )
  )
)
